# InstrumentalAmplifier_in.net
KiCad netlist of a schematic drawn in Altium Designer
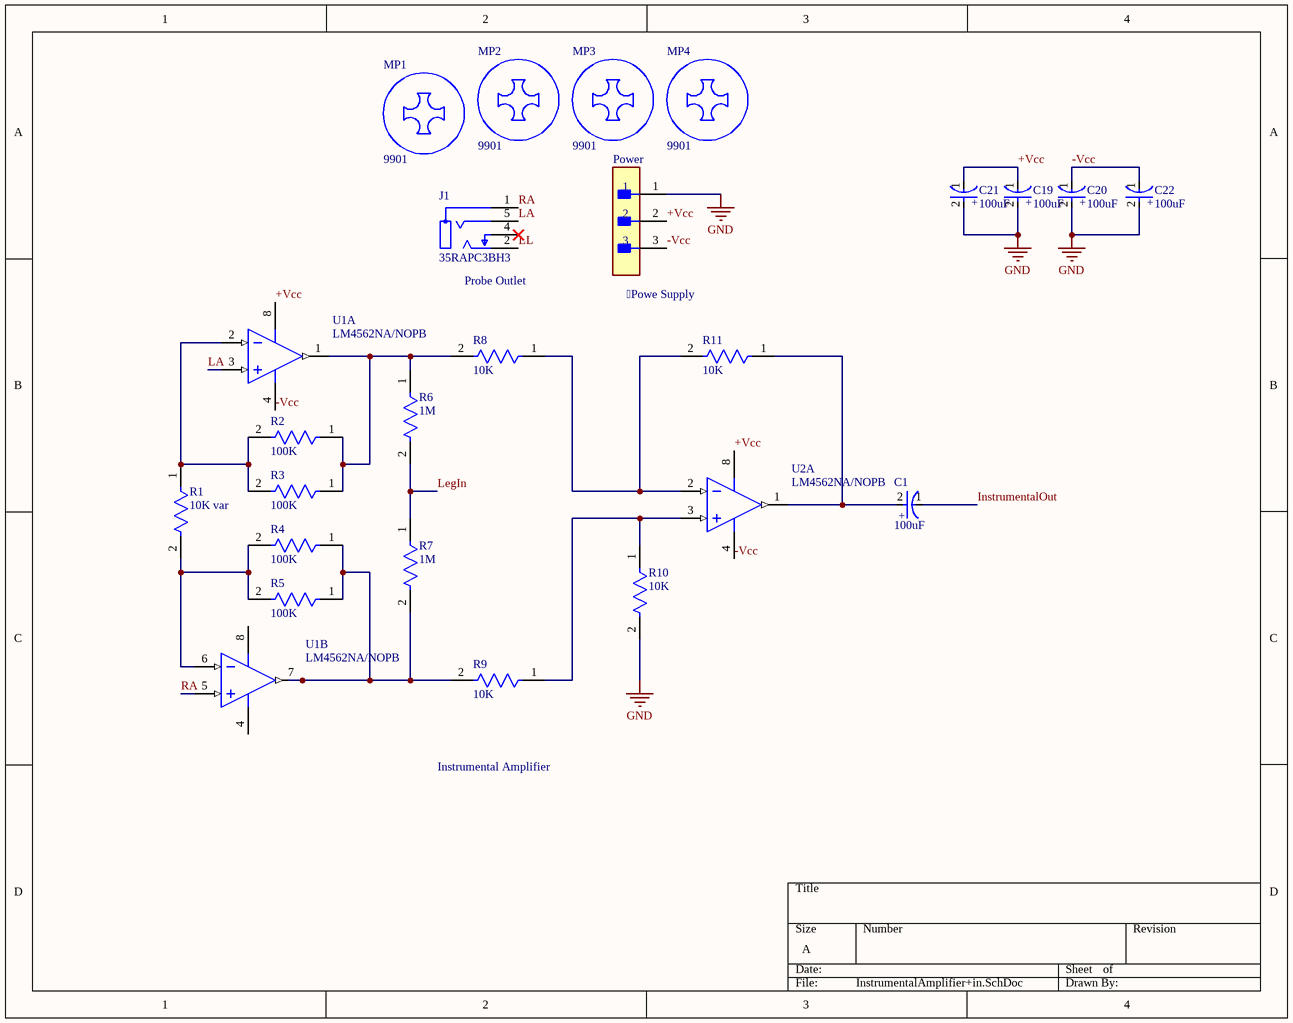
[diagram p0: InstrumentalAmplifier+in.SchDoc]

(export (version "E")
  (design (tool "Eeschema 10.0.6"))
  (components
    (comp (ref "C1")
      (value "100uF")
      (footprint "FP-RAD-TH-D_6_3_0_5-L_11-MFG")
      (description "Aluminum Electrolytic Capacitors (Radial Lead Type) 4.7uF ±20% 160V")
      (fields (field (name "VOLTAGE") "160V") (field (name "TOLERANCE") "20%"))
      (libsource (lib "Altium Content Vault") (part "203bc49f2ac43e59fd269a8c329ed05"))
    )
    (comp (ref "C19")
      (value "100uF")
      (footprint "FP-RAD-TH-D_6_3_0_5-L_11-MFG")
      (description "Aluminum Electrolytic Capacitors (Radial Lead Type) 4.7uF ±20% 160V")
      (fields (field (name "VOLTAGE") "160V") (field (name "TOLERANCE") "20%"))
      (libsource (lib "Altium Content Vault") (part "203bc49f2ac43e59fd269a8c329ed05"))
    )
    (comp (ref "C20")
      (value "100uF")
      (footprint "FP-RAD-TH-D_6_3_0_5-L_11-MFG")
      (description "Aluminum Electrolytic Capacitors (Radial Lead Type) 4.7uF ±20% 160V")
      (fields (field (name "VOLTAGE") "160V") (field (name "TOLERANCE") "20%"))
      (libsource (lib "Altium Content Vault") (part "203bc49f2ac43e59fd269a8c329ed05"))
    )
    (comp (ref "C21")
      (value "100uF")
      (footprint "FP-RAD-TH-D_6_3_0_5-L_11-MFG")
      (description "Aluminum Electrolytic Capacitors (Radial Lead Type) 4.7uF ±20% 160V")
      (fields (field (name "VOLTAGE") "160V") (field (name "TOLERANCE") "20%"))
      (libsource (lib "Altium Content Vault") (part "203bc49f2ac43e59fd269a8c329ed05"))
    )
    (comp (ref "C22")
      (value "100uF")
      (footprint "FP-RAD-TH-D_6_3_0_5-L_11-MFG")
      (description "Aluminum Electrolytic Capacitors (Radial Lead Type) 4.7uF ±20% 160V")
      (fields (field (name "VOLTAGE") "160V") (field (name "TOLERANCE") "20%"))
      (libsource (lib "Altium Content Vault") (part "203bc49f2ac43e59fd269a8c329ed05"))
    )
    (comp (ref "J1")
      (value "35RAPC3BH3")
      (footprint "FP-35RAPC3BH3-MFG")
      (description "CONN JACK STEREO 3.5MM R/A")
      (libsource (lib "Altium Content Vault") (part "6593a1246df2d7246a2ad7da18ee256"))
    )
    (comp (ref "MP1")
      (value "9901")
      (footprint "FP-9901-MFG")
      (description "MACHINE SCREW PAN PHILLIPS 4-40")
      (libsource (lib "Altium Content Vault") (part "00aa4b1e0213c22a4cfa0708b50314e"))
    )
    (comp (ref "MP2")
      (value "9901")
      (footprint "FP-9901-MFG")
      (description "MACHINE SCREW PAN PHILLIPS 4-40")
      (libsource (lib "Altium Content Vault") (part "00aa4b1e0213c22a4cfa0708b50314e"))
    )
    (comp (ref "MP3")
      (value "9901")
      (footprint "FP-9901-MFG")
      (description "MACHINE SCREW PAN PHILLIPS 4-40")
      (libsource (lib "Altium Content Vault") (part "00aa4b1e0213c22a4cfa0708b50314e"))
    )
    (comp (ref "MP4")
      (value "9901")
      (footprint "FP-9901-MFG")
      (description "MACHINE SCREW PAN PHILLIPS 4-40")
      (libsource (lib "Altium Content Vault") (part "00aa4b1e0213c22a4cfa0708b50314e"))
    )
    (comp (ref "Power")
      (value "87224-3")
      (footprint "FP-87224-3-MFG")
      (description "CONN HEADER VERT 3POS 2.54MM")
      (libsource (lib "Altium Content Vault") (part "0d3f023dd272f625e17a2be33dea85f"))
    )
    (comp (ref "R1")
      (value "10K var")
      (footprint "FP-CFR-25-MFG")
      (description "RES 10 OHM 1/4W 5% AXIAL")
      (fields (field (name "TOLERANCE") "5%"))
      (libsource (lib "Altium Content Vault") (part "1029c3af85768c4190bb7ad29bc67b5"))
    )
    (comp (ref "R2")
      (value "100K")
      (footprint "FP-CFR-25-MFG")
      (description "RES 10 OHM 1/4W 5% AXIAL")
      (fields (field (name "TOLERANCE") "5%"))
      (libsource (lib "Altium Content Vault") (part "1029c3af85768c4190bb7ad29bc67b5"))
    )
    (comp (ref "R3")
      (value "100K")
      (footprint "FP-CFR-25-MFG")
      (description "RES 10 OHM 1/4W 5% AXIAL")
      (fields (field (name "TOLERANCE") "5%"))
      (libsource (lib "Altium Content Vault") (part "1029c3af85768c4190bb7ad29bc67b5"))
    )
    (comp (ref "R4")
      (value "100K")
      (footprint "FP-CFR-25-MFG")
      (description "RES 10 OHM 1/4W 5% AXIAL")
      (fields (field (name "TOLERANCE") "5%"))
      (libsource (lib "Altium Content Vault") (part "1029c3af85768c4190bb7ad29bc67b5"))
    )
    (comp (ref "R5")
      (value "100K")
      (footprint "FP-CFR-25-MFG")
      (description "RES 10 OHM 1/4W 5% AXIAL")
      (fields (field (name "TOLERANCE") "5%"))
      (libsource (lib "Altium Content Vault") (part "1029c3af85768c4190bb7ad29bc67b5"))
    )
    (comp (ref "R6")
      (value "1M")
      (footprint "FP-CFR-25-MFG")
      (description "RES 10 OHM 1/4W 5% AXIAL")
      (fields (field (name "TOLERANCE") "5%"))
      (libsource (lib "Altium Content Vault") (part "1029c3af85768c4190bb7ad29bc67b5"))
    )
    (comp (ref "R7")
      (value "1M")
      (footprint "FP-CFR-25-MFG")
      (description "RES 10 OHM 1/4W 5% AXIAL")
      (fields (field (name "TOLERANCE") "5%"))
      (libsource (lib "Altium Content Vault") (part "1029c3af85768c4190bb7ad29bc67b5"))
    )
    (comp (ref "R8")
      (value "10K")
      (footprint "FP-CFR-25-MFG")
      (description "RES 10 OHM 1/4W 5% AXIAL")
      (fields (field (name "TOLERANCE") "5%"))
      (libsource (lib "Altium Content Vault") (part "1029c3af85768c4190bb7ad29bc67b5"))
    )
    (comp (ref "R9")
      (value "10K")
      (footprint "FP-CFR-25-MFG")
      (description "RES 10 OHM 1/4W 5% AXIAL")
      (fields (field (name "TOLERANCE") "5%"))
      (libsource (lib "Altium Content Vault") (part "1029c3af85768c4190bb7ad29bc67b5"))
    )
    (comp (ref "R10")
      (value "10K")
      (footprint "FP-CFR-25-MFG")
      (description "RES 10 OHM 1/4W 5% AXIAL")
      (fields (field (name "TOLERANCE") "5%"))
      (libsource (lib "Altium Content Vault") (part "1029c3af85768c4190bb7ad29bc67b5"))
    )
    (comp (ref "R11")
      (value "10K")
      (footprint "FP-CFR-25-MFG")
      (description "RES 10 OHM 1/4W 5% AXIAL")
      (fields (field (name "TOLERANCE") "5%"))
      (libsource (lib "Altium Content Vault") (part "1029c3af85768c4190bb7ad29bc67b5"))
    )
    (comp (ref "U1")
      (value "LM4562NA/NOPB")
      (footprint "P0008A")
      (description "Dual High Performance, High Fidelity Audio Operational Amplifier, 8-pin MDIP, Pb-Free")
      (fields (field (name "MANUFACTURER") "Texas Instruments"))
      (libsource (lib "Altium Content Vault") (part "AMP-AUDA-LM4562-8"))
    )
    (comp (ref "U2")
      (value "LM4562NA/NOPB")
      (footprint "P0008A")
      (description "Dual High Performance, High Fidelity Audio Operational Amplifier, 8-pin MDIP, Pb-Free")
      (fields (field (name "MANUFACTURER") "Texas Instruments"))
      (libsource (lib "Altium Content Vault") (part "AMP-AUDA-LM4562-8"))
    )
  )
  (nets
    (net (code "1") (name "/+Vcc") (class "Default")
      (node (ref "C19") (pin "1") (pinfunction "C_1") (pintype "passive"))
      (node (ref "C21") (pin "1") (pinfunction "C_1") (pintype "passive"))
      (node (ref "Power") (pin "2") (pinfunction "2_2") (pintype "passive"))
      (node (ref "U1") (pin "8") (pinfunction "V+_8") (pintype "power_in"))
      (node (ref "U2") (pin "8") (pinfunction "V+_8") (pintype "power_in"))
    )
    (net (code "2") (name "/-Vcc") (class "Default")
      (node (ref "C20") (pin "1") (pinfunction "C_1") (pintype "passive"))
      (node (ref "C22") (pin "1") (pinfunction "C_1") (pintype "passive"))
      (node (ref "Power") (pin "3") (pinfunction "3_3") (pintype "passive"))
      (node (ref "U1") (pin "4") (pinfunction "V-_4") (pintype "power_in"))
      (node (ref "U2") (pin "4") (pinfunction "V-_4") (pintype "power_in"))
    )
    (net (code "3") (name "/InstrumentalOut") (class "Default")
      (node (ref "C1") (pin "1") (pinfunction "C_1") (pintype "passive"))
    )
    (net (code "4") (name "/LA") (class "Default")
      (node (ref "J1") (pin "5") (pinfunction "5_5") (pintype "passive"))
      (node (ref "U1") (pin "3") (pinfunction "IN_A_3") (pintype "input"))
    )
    (net (code "5") (name "/LL") (class "Default")
      (node (ref "J1") (pin "2") (pinfunction "2_2") (pintype "passive"))
    )
    (net (code "6") (name "/LegIn") (class "Default")
      (node (ref "R6") (pin "2") (pinfunction "2_2") (pintype "passive"))
      (node (ref "R7") (pin "1") (pinfunction "1_1") (pintype "passive"))
    )
    (net (code "7") (name "/RA") (class "Default")
      (node (ref "J1") (pin "1") (pinfunction "1_1") (pintype "passive"))
      (node (ref "U1") (pin "5") (pinfunction "IN_B_5") (pintype "input"))
    )
    (net (code "8") (name "GND") (class "Default")
      (node (ref "C19") (pin "2") (pinfunction "A_2") (pintype "passive"))
      (node (ref "C20") (pin "2") (pinfunction "A_2") (pintype "passive"))
      (node (ref "C21") (pin "2") (pinfunction "A_2") (pintype "passive"))
      (node (ref "C22") (pin "2") (pinfunction "A_2") (pintype "passive"))
      (node (ref "Power") (pin "1") (pinfunction "1_1") (pintype "passive"))
      (node (ref "R10") (pin "2") (pinfunction "2_2") (pintype "passive"))
    )
    (net (code "9") (name "Net-(C1-A)") (class "Default")
      (node (ref "C1") (pin "2") (pinfunction "A_2") (pintype "passive"))
      (node (ref "R11") (pin "1") (pinfunction "1_1") (pintype "passive"))
      (node (ref "U2") (pin "1") (pinfunction "OUT_A_1") (pintype "output"))
    )
    (net (code "10") (name "Net-(R1-Pad1)") (class "Default")
      (node (ref "R1") (pin "1") (pinfunction "1_1") (pintype "passive"))
      (node (ref "R2") (pin "2") (pinfunction "2_2") (pintype "passive"))
      (node (ref "R3") (pin "2") (pinfunction "2_2") (pintype "passive"))
      (node (ref "U1") (pin "2") (pinfunction "IN_A_2") (pintype "input"))
    )
    (net (code "11") (name "Net-(R1-Pad2)") (class "Default")
      (node (ref "R1") (pin "2") (pinfunction "2_2") (pintype "passive"))
      (node (ref "R4") (pin "2") (pinfunction "2_2") (pintype "passive"))
      (node (ref "R5") (pin "2") (pinfunction "2_2") (pintype "passive"))
      (node (ref "U1") (pin "6") (pinfunction "IN_B_6") (pintype "input"))
    )
    (net (code "12") (name "Net-(R10-Pad1)") (class "Default")
      (node (ref "R10") (pin "1") (pinfunction "1_1") (pintype "passive"))
      (node (ref "R9") (pin "1") (pinfunction "1_1") (pintype "passive"))
      (node (ref "U2") (pin "3") (pinfunction "IN_A_3") (pintype "input"))
    )
    (net (code "13") (name "Net-(R11-Pad2)") (class "Default")
      (node (ref "R11") (pin "2") (pinfunction "2_2") (pintype "passive"))
      (node (ref "R8") (pin "1") (pinfunction "1_1") (pintype "passive"))
      (node (ref "U2") (pin "2") (pinfunction "IN_A_2") (pintype "input"))
    )
    (net (code "14") (name "Net-(U1A-OUT_A)") (class "Default")
      (node (ref "R2") (pin "1") (pinfunction "1_1") (pintype "passive"))
      (node (ref "R3") (pin "1") (pinfunction "1_1") (pintype "passive"))
      (node (ref "R6") (pin "1") (pinfunction "1_1") (pintype "passive"))
      (node (ref "R8") (pin "2") (pinfunction "2_2") (pintype "passive"))
      (node (ref "U1") (pin "1") (pinfunction "OUT_A_1") (pintype "output"))
    )
    (net (code "15") (name "Net-(U1B-OUT_B)") (class "Default")
      (node (ref "R4") (pin "1") (pinfunction "1_1") (pintype "passive"))
      (node (ref "R5") (pin "1") (pinfunction "1_1") (pintype "passive"))
      (node (ref "R7") (pin "2") (pinfunction "2_2") (pintype "passive"))
      (node (ref "R9") (pin "2") (pinfunction "2_2") (pintype "passive"))
      (node (ref "U1") (pin "7") (pinfunction "OUT_B_7") (pintype "output"))
    )
    (net (code "16") (name "unconnected-(J1-Pad4)") (class "Default")
      (node (ref "J1") (pin "4") (pinfunction "4_4") (pintype "passive+no_connect"))
    )
    (net (code "17") (name "unconnected-(U1B-V+-Pad8)") (class "Default")
      (node (ref "U1") (pin "8") (pinfunction "V+_8") (pintype "power_in"))
    )
    (net (code "18") (name "unconnected-(U1B-V--Pad4)") (class "Default")
      (node (ref "U1") (pin "4") (pinfunction "V-_4") (pintype "power_in"))
    )
  )
)
